# PSoC_Devboard_CAN_Cape.net
KiCad netlist of a schematic drawn in Altium Designer
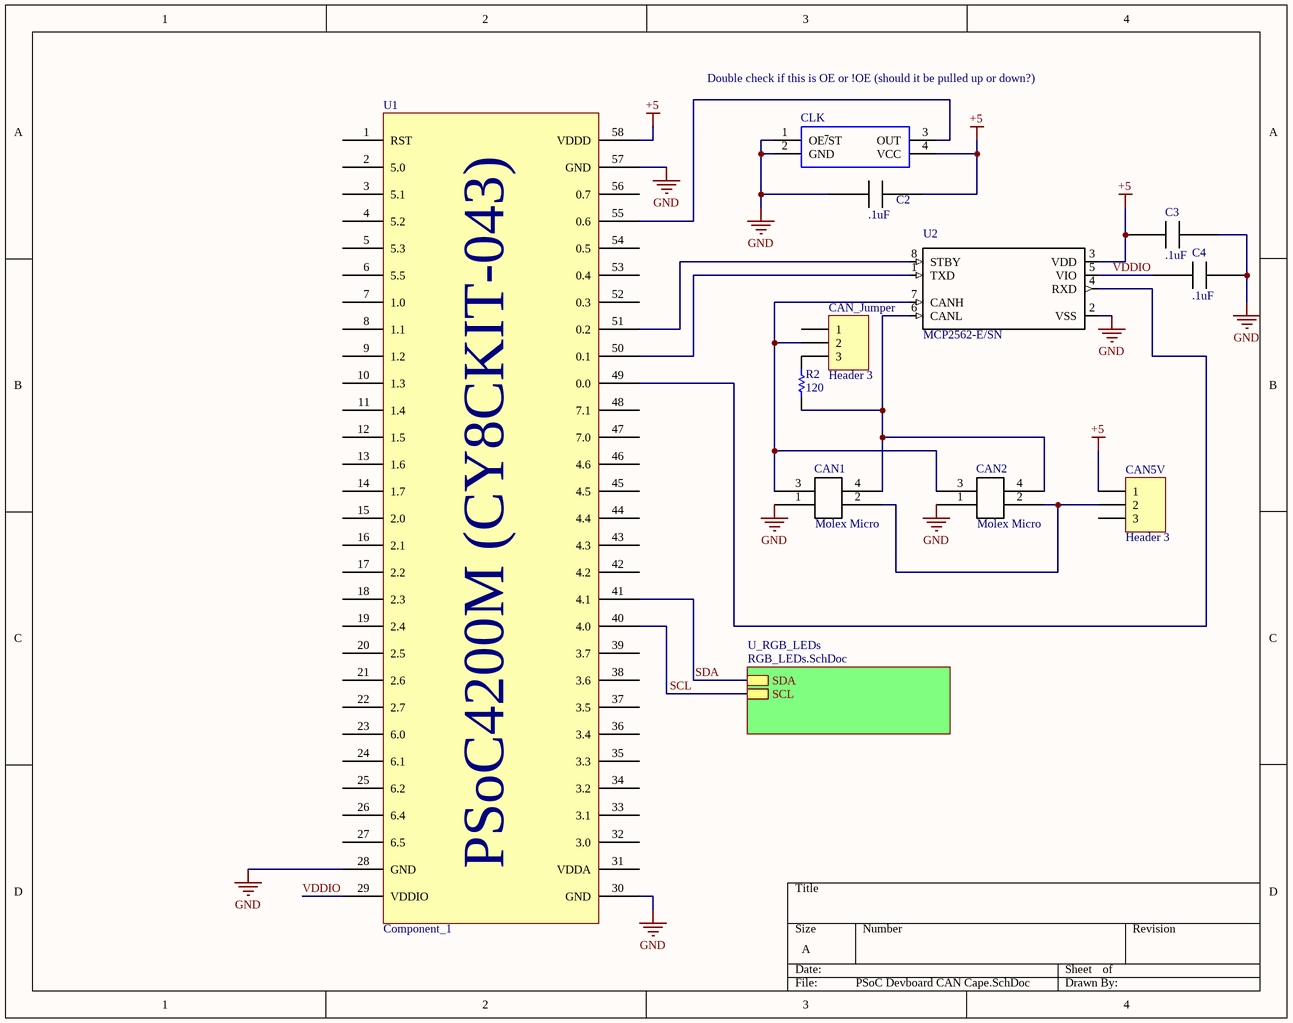
[diagram p0: PSoC Devboard CAN Cape.SchDoc]

(export (version "E")
  (design (tool "Eeschema 10.0.6"))
  (components
    (comp (ref "C2")
      (value ".1uF")
      (footprint "0805")
      (libsource (lib "PSoC Devboard CAN Cape") (part "Cap"))
    )
    (comp (ref "C3")
      (value ".1uF")
      (footprint "0805")
      (libsource (lib "PSoC Devboard CAN Cape") (part "Cap"))
    )
    (comp (ref "C4")
      (value ".1uF")
      (footprint "0805")
      (libsource (lib "PSoC Devboard CAN Cape") (part "Cap"))
    )
    (comp (ref "CAN1")
      (value "Molex Micro")
      (footprint "0430450427")
      (description "Molex micro-fit 3.0, P/N 0430450427")
      (libsource (lib "Husky Robotics Standard Library 2019-2020") (part "Molex micro-fit 4-pin (dual row schematic)"))
    )
    (comp (ref "CAN2")
      (value "Molex Micro")
      (footprint "0430450427")
      (description "Molex micro-fit 3.0, P/N 0430450427")
      (libsource (lib "Husky Robotics Standard Library 2019-2020") (part "Molex micro-fit 4-pin (dual row schematic)"))
    )
    (comp (ref "CAN5V")
      (value "Header 3")
      (footprint "HDR1X3")
      (description "Header, 3-Pin")
      (fields (field (name "PUBLISHER") "Altium Limited"))
      (libsource (lib "Miscellaneous Connectors") (part "Header 3"))
    )
    (comp (ref "CAN_Jumper")
      (value "Header 3")
      (footprint "HDR1X3")
      (description "Header, 3-Pin")
      (fields (field (name "PUBLISHER") "Altium Limited"))
      (libsource (lib "Miscellaneous Connectors") (part "Header 3"))
    )
    (comp (ref "CLK")
      (value "SG-636PCW_50.0000MC3__ROHS")
      (footprint "SG-636")
      (description "Standard Clock Oscillators 50MHz 3.3Volt 100ppm -20C +70C")
      (fields (field (name "MANUFACTURER_PART_NUMBER") "SG-636PCW 50.0000MC3: ROHS"))
      (libsource (lib "Husky Robotics Standard Library 2019-2020") (part "SG-636"))
    )
    (comp (ref "R2")
      (value "120")
      (footprint "RESC0805(2012)_N")
      (description "120R 0.125W 5% 0805 (2012 Metric)  SMD")
      (fields (field (name "TOLERANCE") "5 %") (field (name "POWER") "0.125 W"))
      (libsource (lib "Husky Robotics Standard Library 2019-2020") (part "120R 5% 0805"))
    )
    (comp (ref "U1")
      (value "Component_1")
      (footprint "CY8CKIT-043")
      (libsource (lib "PSoC Devboard CAN Cape") (part "Component_1"))
    )
    (comp (ref "U2")
      (value "MCP2562-E/SN")
      (footprint "SOIC127P600X175-8N")
      (description "Microchip MCP2562-E/SN, CAN Transceiver 1MBps 1-channel IEC 61000-4-2, 8-Pin SOIC")
      (fields (field (name "MF") "Microchip"))
      (libsource (lib "Husky Robotics Standard Library 2019-2020") (part "MCP2562-E/SN"))
    )
  )
  (nets
    (net (code "1") (name "+5") (class "Default")
      (node (ref "C2") (pin "2") (pinfunction "2_2") (pintype "passive"))
      (node (ref "C3") (pin "1") (pinfunction "1_1") (pintype "passive"))
      (node (ref "CAN5V") (pin "1") (pinfunction "1_1") (pintype "passive"))
      (node (ref "CLK") (pin "4") (pinfunction "VCC_4") (pintype "power_in"))
      (node (ref "U1") (pin "58") (pinfunction "VDDD_58") (pintype "passive"))
      (node (ref "U2") (pin "3") (pinfunction "VDD_3") (pintype "power_in"))
    )
    (net (code "2") (name "/SCL") (class "Default")
      (node (ref "U1") (pin "40") (pinfunction "4.0_40") (pintype "passive"))
    )
    (net (code "3") (name "/SDA") (class "Default")
      (node (ref "U1") (pin "41") (pinfunction "4.1_41") (pintype "passive"))
    )
    (net (code "4") (name "/VDDIO") (class "Default")
      (node (ref "C4") (pin "1") (pinfunction "1_1") (pintype "passive"))
      (node (ref "U1") (pin "29") (pinfunction "VDDIO_29") (pintype "passive"))
      (node (ref "U2") (pin "5") (pinfunction "VIO_5") (pintype "power_in"))
    )
    (net (code "5") (name "GND") (class "Default")
      (node (ref "C2") (pin "1") (pinfunction "1_1") (pintype "passive"))
      (node (ref "C3") (pin "2") (pinfunction "2_2") (pintype "passive"))
      (node (ref "C4") (pin "2") (pinfunction "2_2") (pintype "passive"))
      (node (ref "CAN1") (pin "1") (pintype "passive"))
      (node (ref "CAN2") (pin "1") (pintype "passive"))
      (node (ref "CLK") (pin "1") (pinfunction "OE~{/}ST_1") (pintype "passive"))
      (node (ref "CLK") (pin "2") (pinfunction "GND_2") (pintype "passive"))
      (node (ref "U1") (pin "28") (pinfunction "GND_28") (pintype "passive"))
      (node (ref "U1") (pin "30") (pinfunction "GND_30") (pintype "passive"))
      (node (ref "U1") (pin "57") (pinfunction "GND_57") (pintype "passive"))
      (node (ref "U2") (pin "2") (pinfunction "VSS_2") (pintype "power_in"))
    )
    (net (code "6") (name "Net-(CAN1-Pad2)") (class "Default")
      (node (ref "CAN1") (pin "2") (pintype "passive"))
      (node (ref "CAN2") (pin "2") (pintype "passive"))
      (node (ref "CAN5V") (pin "2") (pinfunction "2_2") (pintype "passive"))
    )
    (net (code "7") (name "Net-(CAN_Jumper-Pad3)") (class "Default")
      (node (ref "CAN_Jumper") (pin "3") (pinfunction "3_3") (pintype "passive"))
      (node (ref "R2") (pin "2") (pinfunction "2_2") (pintype "passive"))
    )
    (net (code "8") (name "Net-(CLK-OUT)") (class "Default")
      (node (ref "CLK") (pin "3") (pinfunction "OUT_3") (pintype "passive"))
      (node (ref "U1") (pin "55") (pinfunction "0.6_55") (pintype "passive"))
    )
    (net (code "9") (name "Net-(U1-0.0)") (class "Default")
      (node (ref "U1") (pin "49") (pinfunction "0.0_49") (pintype "passive"))
      (node (ref "U2") (pin "4") (pinfunction "RXD_4") (pintype "output"))
    )
    (net (code "10") (name "Net-(U1-0.1)") (class "Default")
      (node (ref "U1") (pin "50") (pinfunction "0.1_50") (pintype "passive"))
      (node (ref "U2") (pin "1") (pinfunction "TXD_1") (pintype "input"))
    )
    (net (code "11") (name "Net-(U1-0.2)") (class "Default")
      (node (ref "U1") (pin "51") (pinfunction "0.2_51") (pintype "passive"))
      (node (ref "U2") (pin "8") (pinfunction "STBY_8") (pintype "input"))
    )
    (net (code "12") (name "Net-(U2-CANH)") (class "Default")
      (node (ref "CAN1") (pin "3") (pintype "passive"))
      (node (ref "CAN2") (pin "3") (pintype "passive"))
      (node (ref "CAN_Jumper") (pin "2") (pinfunction "2_2") (pintype "passive"))
      (node (ref "U2") (pin "7") (pinfunction "CANH_7") (pintype "input"))
    )
    (net (code "13") (name "Net-(U2-CANL)") (class "Default")
      (node (ref "CAN1") (pin "4") (pintype "passive"))
      (node (ref "CAN2") (pin "4") (pintype "passive"))
      (node (ref "R2") (pin "1") (pinfunction "1_1") (pintype "passive"))
      (node (ref "U2") (pin "6") (pinfunction "CANL_6") (pintype "input"))
    )
    (net (code "14") (name "unconnected-(CAN5V-Pad3)") (class "Default")
      (node (ref "CAN5V") (pin "3") (pinfunction "3_3") (pintype "passive"))
    )
    (net (code "15") (name "unconnected-(CAN_Jumper-Pad1)") (class "Default")
      (node (ref "CAN_Jumper") (pin "1") (pinfunction "1_1") (pintype "passive"))
    )
    (net (code "16") (name "unconnected-(U1-0.3-Pad52)") (class "Default")
      (node (ref "U1") (pin "52") (pinfunction "0.3_52") (pintype "passive"))
    )
    (net (code "17") (name "unconnected-(U1-0.4-Pad53)") (class "Default")
      (node (ref "U1") (pin "53") (pinfunction "0.4_53") (pintype "passive"))
    )
    (net (code "18") (name "unconnected-(U1-0.5-Pad54)") (class "Default")
      (node (ref "U1") (pin "54") (pinfunction "0.5_54") (pintype "passive"))
    )
    (net (code "19") (name "unconnected-(U1-0.7-Pad56)") (class "Default")
      (node (ref "U1") (pin "56") (pinfunction "0.7_56") (pintype "passive"))
    )
    (net (code "20") (name "unconnected-(U1-1.0-Pad7)") (class "Default")
      (node (ref "U1") (pin "7") (pinfunction "1.0_7") (pintype "passive"))
    )
    (net (code "21") (name "unconnected-(U1-1.1-Pad8)") (class "Default")
      (node (ref "U1") (pin "8") (pinfunction "1.1_8") (pintype "passive"))
    )
    (net (code "22") (name "unconnected-(U1-1.2-Pad9)") (class "Default")
      (node (ref "U1") (pin "9") (pinfunction "1.2_9") (pintype "passive"))
    )
    (net (code "23") (name "unconnected-(U1-1.3-Pad10)") (class "Default")
      (node (ref "U1") (pin "10") (pinfunction "1.3_10") (pintype "passive"))
    )
    (net (code "24") (name "unconnected-(U1-1.4-Pad11)") (class "Default")
      (node (ref "U1") (pin "11") (pinfunction "1.4_11") (pintype "passive"))
    )
    (net (code "25") (name "unconnected-(U1-1.5-Pad12)") (class "Default")
      (node (ref "U1") (pin "12") (pinfunction "1.5_12") (pintype "passive"))
    )
    (net (code "26") (name "unconnected-(U1-1.6-Pad13)") (class "Default")
      (node (ref "U1") (pin "13") (pinfunction "1.6_13") (pintype "passive"))
    )
    (net (code "27") (name "unconnected-(U1-1.7-Pad14)") (class "Default")
      (node (ref "U1") (pin "14") (pinfunction "1.7_14") (pintype "passive"))
    )
    (net (code "28") (name "unconnected-(U1-2.0-Pad15)") (class "Default")
      (node (ref "U1") (pin "15") (pinfunction "2.0_15") (pintype "passive"))
    )
    (net (code "29") (name "unconnected-(U1-2.1-Pad16)") (class "Default")
      (node (ref "U1") (pin "16") (pinfunction "2.1_16") (pintype "passive"))
    )
    (net (code "30") (name "unconnected-(U1-2.2-Pad17)") (class "Default")
      (node (ref "U1") (pin "17") (pinfunction "2.2_17") (pintype "passive"))
    )
    (net (code "31") (name "unconnected-(U1-2.3-Pad18)") (class "Default")
      (node (ref "U1") (pin "18") (pinfunction "2.3_18") (pintype "passive"))
    )
    (net (code "32") (name "unconnected-(U1-2.4-Pad19)") (class "Default")
      (node (ref "U1") (pin "19") (pinfunction "2.4_19") (pintype "passive"))
    )
    (net (code "33") (name "unconnected-(U1-2.5-Pad20)") (class "Default")
      (node (ref "U1") (pin "20") (pinfunction "2.5_20") (pintype "passive"))
    )
    (net (code "34") (name "unconnected-(U1-2.6-Pad21)") (class "Default")
      (node (ref "U1") (pin "21") (pinfunction "2.6_21") (pintype "passive"))
    )
    (net (code "35") (name "unconnected-(U1-2.7-Pad22)") (class "Default")
      (node (ref "U1") (pin "22") (pinfunction "2.7_22") (pintype "passive"))
    )
    (net (code "36") (name "unconnected-(U1-3.0-Pad32)") (class "Default")
      (node (ref "U1") (pin "32") (pinfunction "3.0_32") (pintype "passive"))
    )
    (net (code "37") (name "unconnected-(U1-3.1-Pad33)") (class "Default")
      (node (ref "U1") (pin "33") (pinfunction "3.1_33") (pintype "passive"))
    )
    (net (code "38") (name "unconnected-(U1-3.2-Pad34)") (class "Default")
      (node (ref "U1") (pin "34") (pinfunction "3.2_34") (pintype "passive"))
    )
    (net (code "39") (name "unconnected-(U1-3.3-Pad35)") (class "Default")
      (node (ref "U1") (pin "35") (pinfunction "3.3_35") (pintype "passive"))
    )
    (net (code "40") (name "unconnected-(U1-3.4-Pad36)") (class "Default")
      (node (ref "U1") (pin "36") (pinfunction "3.4_36") (pintype "passive"))
    )
    (net (code "41") (name "unconnected-(U1-3.5-Pad37)") (class "Default")
      (node (ref "U1") (pin "37") (pinfunction "3.5_37") (pintype "passive"))
    )
    (net (code "42") (name "unconnected-(U1-3.6-Pad38)") (class "Default")
      (node (ref "U1") (pin "38") (pinfunction "3.6_38") (pintype "passive"))
    )
    (net (code "43") (name "unconnected-(U1-3.7-Pad39)") (class "Default")
      (node (ref "U1") (pin "39") (pinfunction "3.7_39") (pintype "passive"))
    )
    (net (code "44") (name "unconnected-(U1-4.2-Pad42)") (class "Default")
      (node (ref "U1") (pin "42") (pinfunction "4.2_42") (pintype "passive"))
    )
    (net (code "45") (name "unconnected-(U1-4.3-Pad43)") (class "Default")
      (node (ref "U1") (pin "43") (pinfunction "4.3_43") (pintype "passive"))
    )
    (net (code "46") (name "unconnected-(U1-4.4-Pad44)") (class "Default")
      (node (ref "U1") (pin "44") (pinfunction "4.4_44") (pintype "passive"))
    )
    (net (code "47") (name "unconnected-(U1-4.5-Pad45)") (class "Default")
      (node (ref "U1") (pin "45") (pinfunction "4.5_45") (pintype "passive"))
    )
    (net (code "48") (name "unconnected-(U1-4.6-Pad46)") (class "Default")
      (node (ref "U1") (pin "46") (pinfunction "4.6_46") (pintype "passive"))
    )
    (net (code "49") (name "unconnected-(U1-5.0-Pad2)") (class "Default")
      (node (ref "U1") (pin "2") (pinfunction "5.0_2") (pintype "passive"))
    )
    (net (code "50") (name "unconnected-(U1-5.1-Pad3)") (class "Default")
      (node (ref "U1") (pin "3") (pinfunction "5.1_3") (pintype "passive"))
    )
    (net (code "51") (name "unconnected-(U1-5.2-Pad4)") (class "Default")
      (node (ref "U1") (pin "4") (pinfunction "5.2_4") (pintype "passive"))
    )
    (net (code "52") (name "unconnected-(U1-5.3-Pad5)") (class "Default")
      (node (ref "U1") (pin "5") (pinfunction "5.3_5") (pintype "passive"))
    )
    (net (code "53") (name "unconnected-(U1-5.5-Pad6)") (class "Default")
      (node (ref "U1") (pin "6") (pinfunction "5.5_6") (pintype "passive"))
    )
    (net (code "54") (name "unconnected-(U1-6.0-Pad23)") (class "Default")
      (node (ref "U1") (pin "23") (pinfunction "6.0_23") (pintype "passive"))
    )
    (net (code "55") (name "unconnected-(U1-6.1-Pad24)") (class "Default")
      (node (ref "U1") (pin "24") (pinfunction "6.1_24") (pintype "passive"))
    )
    (net (code "56") (name "unconnected-(U1-6.2-Pad25)") (class "Default")
      (node (ref "U1") (pin "25") (pinfunction "6.2_25") (pintype "passive"))
    )
    (net (code "57") (name "unconnected-(U1-6.4-Pad26)") (class "Default")
      (node (ref "U1") (pin "26") (pinfunction "6.4_26") (pintype "passive"))
    )
    (net (code "58") (name "unconnected-(U1-6.5-Pad27)") (class "Default")
      (node (ref "U1") (pin "27") (pinfunction "6.5_27") (pintype "passive"))
    )
    (net (code "59") (name "unconnected-(U1-7.0-Pad47)") (class "Default")
      (node (ref "U1") (pin "47") (pinfunction "7.0_47") (pintype "passive"))
    )
    (net (code "60") (name "unconnected-(U1-7.1-Pad48)") (class "Default")
      (node (ref "U1") (pin "48") (pinfunction "7.1_48") (pintype "passive"))
    )
    (net (code "61") (name "unconnected-(U1-RST-Pad1)") (class "Default")
      (node (ref "U1") (pin "1") (pinfunction "RST_1") (pintype "passive"))
    )
    (net (code "62") (name "unconnected-(U1-VDDA-Pad31)") (class "Default")
      (node (ref "U1") (pin "31") (pinfunction "VDDA_31") (pintype "passive"))
    )
  )
)
